# phone.net
KiCad netlist of a schematic drawn in Altium Designer
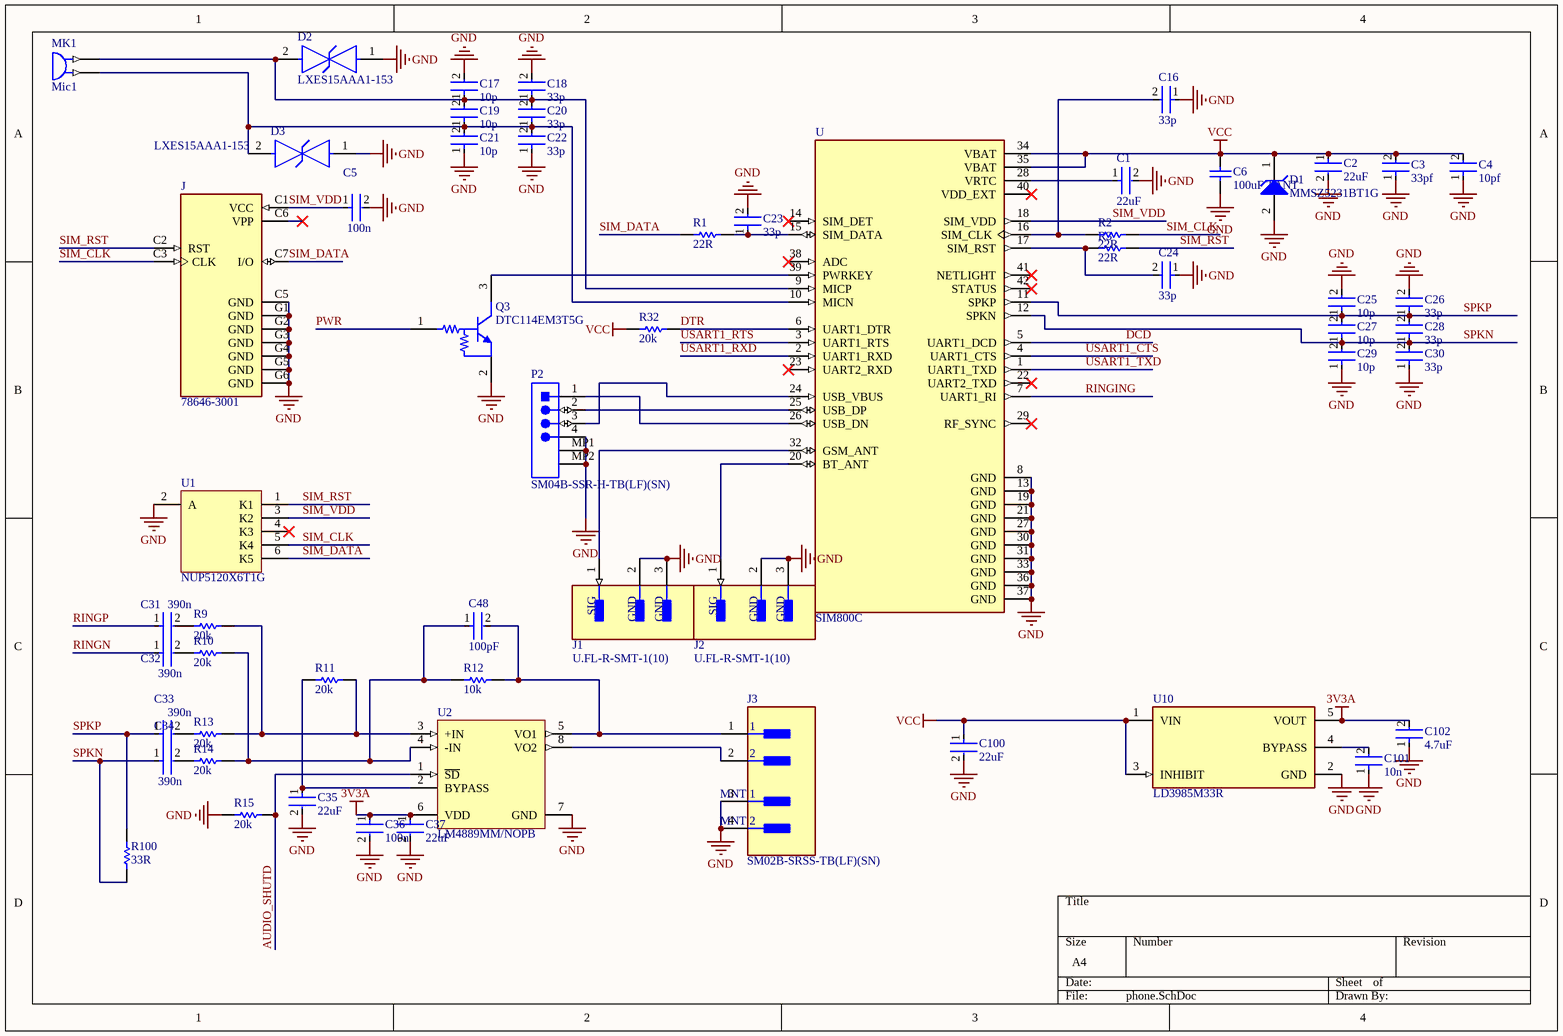
[diagram p0: phone.SchDoc]

(export (version "E")
  (design (tool "Eeschema 10.0.6"))
  (components
    (comp (ref "C1")
      (value "22uF")
      (footprint "FP-GRM21B-0_15-MFG")
      (description "Chip Multilayer Ceramic Capacitors for General Purpose, 0805, 22uF, X5R, 15%, 20%, 6.3V")
      (fields (field (name "VOLTAGE") "6.3V") (field (name "TOLERANCE") "20%"))
      (libsource (lib "Altium Content Vault") (part "b4654b650e69147ec39a6b967a45e02"))
    )
    (comp (ref "C2")
      (value "22uF")
      (footprint "FP-GRM21B-0_15-MFG")
      (description "Chip Multilayer Ceramic Capacitors for General Purpose, 0805, 22uF, X5R, 15%, 20%, 6.3V")
      (fields (field (name "VOLTAGE") "6.3V") (field (name "TOLERANCE") "20%"))
      (libsource (lib "Altium Content Vault") (part "b4654b650e69147ec39a6b967a45e02"))
    )
    (comp (ref "C3")
      (value "33pf")
      (footprint "FP-GRM155-0_05-IPC_A")
      (description "Chip Multilayer Ceramic Capacitors for General Purpose, 0402, 470pF, C0G, 30ppm/°C, 5%, 50V")
      (fields (field (name "VOLTAGE") "50V") (field (name "TOLERANCE") "5%"))
      (libsource (lib "Altium Content Vault") (part "02cd4be3c70576c341d710602a673aa"))
    )
    (comp (ref "C4")
      (value "10pf")
      (footprint "FP-GRM155-0_05-IPC_A")
      (description "Chip Multilayer Ceramic Capacitors for General Purpose, 0402, 470pF, C0G, 30ppm/°C, 5%, 50V")
      (fields (field (name "VOLTAGE") "50V") (field (name "TOLERANCE") "5%"))
      (libsource (lib "Altium Content Vault") (part "02cd4be3c70576c341d710602a673aa"))
    )
    (comp (ref "C5")
      (value "100n")
      (footprint "FP-GRM155-0_05-IPC_A")
      (description "Chip Multilayer Ceramic Capacitors for General Purpose, 0402, 470pF, C0G, 30ppm/°C, 5%, 50V")
      (fields (field (name "VOLTAGE") "50V") (field (name "TOLERANCE") "5%"))
      (libsource (lib "Altium Content Vault") (part "02cd4be3c70576c341d710602a673aa"))
    )
    (comp (ref "C6")
      (value "100uF TANT")
      (footprint "CAPMP3525X20N")
      (description "Capacitor")
      (libsource (lib "Simulation Generic Components") (part "Capacitor"))
    )
    (comp (ref "C16")
      (value "33p")
      (footprint "FP-GRM155-0_05-IPC_A")
      (description "Chip Multilayer Ceramic Capacitors for General Purpose, 0402, 470pF, C0G, 30ppm/°C, 5%, 50V")
      (fields (field (name "VOLTAGE") "50V") (field (name "TOLERANCE") "5%"))
      (libsource (lib "Altium Content Vault") (part "02cd4be3c70576c341d710602a673aa"))
    )
    (comp (ref "C17")
      (value "10p")
      (footprint "FP-GRM155-0_05-IPC_A")
      (description "Chip Multilayer Ceramic Capacitors for General Purpose, 0402, 470pF, C0G, 30ppm/°C, 5%, 50V")
      (fields (field (name "VOLTAGE") "50V") (field (name "TOLERANCE") "5%"))
      (libsource (lib "Altium Content Vault") (part "02cd4be3c70576c341d710602a673aa"))
    )
    (comp (ref "C18")
      (value "33p")
      (footprint "FP-GRM155-0_05-IPC_A")
      (description "Chip Multilayer Ceramic Capacitors for General Purpose, 0402, 470pF, C0G, 30ppm/°C, 5%, 50V")
      (fields (field (name "VOLTAGE") "50V") (field (name "TOLERANCE") "5%"))
      (libsource (lib "Altium Content Vault") (part "02cd4be3c70576c341d710602a673aa"))
    )
    (comp (ref "C19")
      (value "10p")
      (footprint "FP-GRM155-0_05-IPC_A")
      (description "Chip Multilayer Ceramic Capacitors for General Purpose, 0402, 470pF, C0G, 30ppm/°C, 5%, 50V")
      (fields (field (name "VOLTAGE") "50V") (field (name "TOLERANCE") "5%"))
      (libsource (lib "Altium Content Vault") (part "02cd4be3c70576c341d710602a673aa"))
    )
    (comp (ref "C20")
      (value "33p")
      (footprint "FP-GRM155-0_05-IPC_A")
      (description "Chip Multilayer Ceramic Capacitors for General Purpose, 0402, 470pF, C0G, 30ppm/°C, 5%, 50V")
      (fields (field (name "VOLTAGE") "50V") (field (name "TOLERANCE") "5%"))
      (libsource (lib "Altium Content Vault") (part "02cd4be3c70576c341d710602a673aa"))
    )
    (comp (ref "C21")
      (value "10p")
      (footprint "FP-GRM155-0_05-IPC_A")
      (description "Chip Multilayer Ceramic Capacitors for General Purpose, 0402, 470pF, C0G, 30ppm/°C, 5%, 50V")
      (fields (field (name "VOLTAGE") "50V") (field (name "TOLERANCE") "5%"))
      (libsource (lib "Altium Content Vault") (part "02cd4be3c70576c341d710602a673aa"))
    )
    (comp (ref "C22")
      (value "33p")
      (footprint "FP-GRM155-0_05-IPC_A")
      (description "Chip Multilayer Ceramic Capacitors for General Purpose, 0402, 470pF, C0G, 30ppm/°C, 5%, 50V")
      (fields (field (name "VOLTAGE") "50V") (field (name "TOLERANCE") "5%"))
      (libsource (lib "Altium Content Vault") (part "02cd4be3c70576c341d710602a673aa"))
    )
    (comp (ref "C23")
      (value "33p")
      (footprint "FP-GRM155-0_05-IPC_A")
      (description "Chip Multilayer Ceramic Capacitors for General Purpose, 0402, 470pF, C0G, 30ppm/°C, 5%, 50V")
      (fields (field (name "VOLTAGE") "50V") (field (name "TOLERANCE") "5%"))
      (libsource (lib "Altium Content Vault") (part "02cd4be3c70576c341d710602a673aa"))
    )
    (comp (ref "C24")
      (value "33p")
      (footprint "FP-GRM155-0_05-IPC_A")
      (description "Chip Multilayer Ceramic Capacitors for General Purpose, 0402, 470pF, C0G, 30ppm/°C, 5%, 50V")
      (fields (field (name "VOLTAGE") "50V") (field (name "TOLERANCE") "5%"))
      (libsource (lib "Altium Content Vault") (part "02cd4be3c70576c341d710602a673aa"))
    )
    (comp (ref "C25")
      (value "10p")
      (footprint "FP-GRM155-0_05-IPC_A")
      (description "Chip Multilayer Ceramic Capacitors for General Purpose, 0402, 470pF, C0G, 30ppm/°C, 5%, 50V")
      (fields (field (name "VOLTAGE") "50V") (field (name "TOLERANCE") "5%"))
      (libsource (lib "Altium Content Vault") (part "02cd4be3c70576c341d710602a673aa"))
    )
    (comp (ref "C26")
      (value "33p")
      (footprint "FP-GRM155-0_05-IPC_A")
      (description "Chip Multilayer Ceramic Capacitors for General Purpose, 0402, 470pF, C0G, 30ppm/°C, 5%, 50V")
      (fields (field (name "VOLTAGE") "50V") (field (name "TOLERANCE") "5%"))
      (libsource (lib "Altium Content Vault") (part "02cd4be3c70576c341d710602a673aa"))
    )
    (comp (ref "C27")
      (value "10p")
      (footprint "FP-GRM155-0_05-IPC_A")
      (description "Chip Multilayer Ceramic Capacitors for General Purpose, 0402, 470pF, C0G, 30ppm/°C, 5%, 50V")
      (fields (field (name "VOLTAGE") "50V") (field (name "TOLERANCE") "5%"))
      (libsource (lib "Altium Content Vault") (part "02cd4be3c70576c341d710602a673aa"))
    )
    (comp (ref "C28")
      (value "33p")
      (footprint "FP-GRM155-0_05-IPC_A")
      (description "Chip Multilayer Ceramic Capacitors for General Purpose, 0402, 470pF, C0G, 30ppm/°C, 5%, 50V")
      (fields (field (name "VOLTAGE") "50V") (field (name "TOLERANCE") "5%"))
      (libsource (lib "Altium Content Vault") (part "02cd4be3c70576c341d710602a673aa"))
    )
    (comp (ref "C29")
      (value "10p")
      (footprint "FP-GRM155-0_05-IPC_A")
      (description "Chip Multilayer Ceramic Capacitors for General Purpose, 0402, 470pF, C0G, 30ppm/°C, 5%, 50V")
      (fields (field (name "VOLTAGE") "50V") (field (name "TOLERANCE") "5%"))
      (libsource (lib "Altium Content Vault") (part "02cd4be3c70576c341d710602a673aa"))
    )
    (comp (ref "C30")
      (value "33p")
      (footprint "FP-GRM155-0_05-IPC_A")
      (description "Chip Multilayer Ceramic Capacitors for General Purpose, 0402, 470pF, C0G, 30ppm/°C, 5%, 50V")
      (fields (field (name "VOLTAGE") "50V") (field (name "TOLERANCE") "5%"))
      (libsource (lib "Altium Content Vault") (part "02cd4be3c70576c341d710602a673aa"))
    )
    (comp (ref "C31")
      (value "390n")
      (footprint "FP-GRM155-0_05-IPC_A")
      (description "Chip Multilayer Ceramic Capacitors for General Purpose, 0402, 470pF, C0G, 30ppm/°C, 5%, 50V")
      (fields (field (name "VOLTAGE") "50V") (field (name "TOLERANCE") "5%"))
      (libsource (lib "Altium Content Vault") (part "02cd4be3c70576c341d710602a673aa"))
    )
    (comp (ref "C32")
      (value "390n")
      (footprint "FP-GRM155-0_05-IPC_A")
      (description "Chip Multilayer Ceramic Capacitors for General Purpose, 0402, 470pF, C0G, 30ppm/°C, 5%, 50V")
      (fields (field (name "VOLTAGE") "50V") (field (name "TOLERANCE") "5%"))
      (libsource (lib "Altium Content Vault") (part "02cd4be3c70576c341d710602a673aa"))
    )
    (comp (ref "C33")
      (value "390n")
      (footprint "FP-GRM155-0_05-IPC_A")
      (description "Chip Multilayer Ceramic Capacitors for General Purpose, 0402, 470pF, C0G, 30ppm/°C, 5%, 50V")
      (fields (field (name "VOLTAGE") "50V") (field (name "TOLERANCE") "5%"))
      (libsource (lib "Altium Content Vault") (part "02cd4be3c70576c341d710602a673aa"))
    )
    (comp (ref "C34")
      (value "390n")
      (footprint "FP-GRM155-0_05-IPC_A")
      (description "Chip Multilayer Ceramic Capacitors for General Purpose, 0402, 470pF, C0G, 30ppm/°C, 5%, 50V")
      (fields (field (name "VOLTAGE") "50V") (field (name "TOLERANCE") "5%"))
      (libsource (lib "Altium Content Vault") (part "02cd4be3c70576c341d710602a673aa"))
    )
    (comp (ref "C35")
      (value "22uF")
      (footprint "FP-GRM21B-0_15-MFG")
      (description "Chip Multilayer Ceramic Capacitors for General Purpose, 0805, 22uF, X5R, 15%, 20%, 6.3V")
      (fields (field (name "VOLTAGE") "6.3V") (field (name "TOLERANCE") "20%"))
      (libsource (lib "Altium Content Vault") (part "b4654b650e69147ec39a6b967a45e02"))
    )
    (comp (ref "C36")
      (value "100n")
      (footprint "FP-GRM155-0_05-IPC_A")
      (description "Chip Multilayer Ceramic Capacitors for General Purpose, 0402, 470pF, C0G, 30ppm/°C, 5%, 50V")
      (fields (field (name "VOLTAGE") "50V") (field (name "TOLERANCE") "5%"))
      (libsource (lib "Altium Content Vault") (part "02cd4be3c70576c341d710602a673aa"))
    )
    (comp (ref "C37")
      (value "22uF")
      (footprint "FP-GRM21B-0_15-MFG")
      (description "Chip Multilayer Ceramic Capacitors for General Purpose, 0805, 22uF, X5R, 15%, 20%, 6.3V")
      (fields (field (name "VOLTAGE") "6.3V") (field (name "TOLERANCE") "20%"))
      (libsource (lib "Altium Content Vault") (part "b4654b650e69147ec39a6b967a45e02"))
    )
    (comp (ref "C48")
      (value "100pF")
      (footprint "FP-GRM155-0_05-IPC_A")
      (description "Chip Multilayer Ceramic Capacitors for General Purpose, 0402, 470pF, C0G, 30ppm/°C, 5%, 50V")
      (fields (field (name "VOLTAGE") "50V") (field (name "TOLERANCE") "5%"))
      (libsource (lib "Altium Content Vault") (part "02cd4be3c70576c341d710602a673aa"))
    )
    (comp (ref "C100")
      (value "22uF")
      (footprint "FP-GRM21B-0_15-MFG")
      (description "Chip Multilayer Ceramic Capacitors for General Purpose, 0805, 22uF, X5R, 15%, 20%, 6.3V")
      (fields (field (name "VOLTAGE") "6.3V") (field (name "TOLERANCE") "20%"))
      (libsource (lib "Altium Content Vault") (part "b4654b650e69147ec39a6b967a45e02"))
    )
    (comp (ref "C101")
      (value "10n")
      (footprint "FP-GRM155-0_05-IPC_A")
      (description "Chip Multilayer Ceramic Capacitors for General Purpose, 0402, 470pF, C0G, 30ppm/°C, 5%, 50V")
      (fields (field (name "VOLTAGE") "50V") (field (name "TOLERANCE") "5%"))
      (libsource (lib "Altium Content Vault") (part "02cd4be3c70576c341d710602a673aa"))
    )
    (comp (ref "C102")
      (value "4.7uF")
      (footprint "FP-GRM188-0_1-e0_2_0_55-IPC_A")
      (description "Chip Multilayer Ceramic Capacitors for General Purpose, 0603, 10uF, X5R, 15%, 20%, 6.3V")
      (fields (field (name "VOLTAGE") "6.3V") (field (name "TOLERANCE") "20%"))
      (libsource (lib "Altium Content Vault") (part "02cd4be3c70576c341d710602a673aa"))
    )
    (comp (ref "D1")
      (value "MMSZ5231BT1G")
      (footprint "ONSC-SOD-123-2-425-04_V")
      (description "Zener Voltage Regulator, 500 mW, 2-Pin SOD-123, Pb-Free, Tape and Reel")
      (fields (field (name "MANUFACTURER") "On Semiconductor"))
      (libsource (lib "Altium Content Vault") (part "ONSC-K1A2-2"))
    )
    (comp (ref "D2")
      (value "LXES15AAA1-153")
      (footprint "FP-LXES15-MFG")
      (description "TVS DIODE 4V 1005")
      (libsource (lib "Altium Content Vault") (part "876f4347bf90aa6f500f43e3cd03972"))
    )
    (comp (ref "D3")
      (value "LXES15AAA1-153")
      (footprint "FP-LXES15-MFG")
      (description "TVS DIODE 4V 1005")
      (libsource (lib "Altium Content Vault") (part "876f4347bf90aa6f500f43e3cd03972"))
    )
    (comp (ref "J")
      (value "78646-3001")
      (footprint "MOLEX_78646-3001")
      (description "6 Position Card Connector Micro SIM Surface Mount, Right Angle Gold")
      (fields (field (name "MF") "Molex"))
      (libsource (lib "SnapEDAsch") (part "78646-3001"))
    )
    (comp (ref "J1")
      (value "U.FL-R-SMT-1(10)")
      (footprint "FP-U_FL-R-SMT-1_10-MFG")
      (description "CONN U.FL RCPT STR 50 OHM SMD")
      (libsource (lib "Altium Content Vault") (part "7158abf7d987fa84906f6fb0d115710"))
    )
    (comp (ref "J2")
      (value "U.FL-R-SMT-1(10)")
      (footprint "FP-U_FL-R-SMT-1_10-MFG")
      (description "CONN U.FL RCPT STR 50 OHM SMD")
      (libsource (lib "Altium Content Vault") (part "7158abf7d987fa84906f6fb0d115710"))
    )
    (comp (ref "J3")
      (value "SM02B-SRSS-TB(LF)(SN)")
      (footprint "FP-SM02B-SRSS-TB_LF_SN-0")
      (description "CONN HEADER SMD R/A 2POS 1MM")
      (libsource (lib "Altium Content Vault") (part "e34efe21362d63d7198b5d2c73e37bd"))
    )
    (comp (ref "MK1")
      (value "Mic1")
      (footprint "4015")
      (description "Microphone")
      (fields (field (name "PUBLISHER") "Altium Limited"))
      (libsource (lib "Miscellaneous Devices") (part "Mic1"))
    )
    (comp (ref "P2")
      (value "SM04B-SSR-H-TB(LF)(SN)")
      (footprint "JST-SM04B-SSR-H-TB_V")
      (description "SSR Connector, Pitch 1 mm, 1 x 4 Position, Height 2 mm, -20 to 85 degC, RoHS, Tape and Reel")
      (fields (field (name "MANUFACTURER") "JST"))
      (libsource (lib "Altium Content Vault") (part "CN-1P-2M-R4_A"))
    )
    (comp (ref "Q3")
      (value "DTC114EM3T5G")
      (footprint "ONSC-SOT-723-3-631AA-01_V")
      (fields (field (name "MANUFACTURER") "On Semiconductor"))
      (libsource (lib "Altium Content Vault") (part "ONSC-BRT-NPN-B1E2C3-3"))
    )
    (comp (ref "R1")
      (value "22R")
      (footprint "RESC1005X40X25NL05T10")
      (fields (field (name "MANUFACTURER") "Yageo / Phycomp") (field (name "PART NUMBER") "RC0402JR-070RL"))
      (libsource (lib "Altium Content Vault") (part "RES"))
    )
    (comp (ref "R2")
      (value "22R")
      (footprint "RESC1005X40X25NL05T10")
      (fields (field (name "MANUFACTURER") "Yageo / Phycomp") (field (name "PART NUMBER") "RC0402JR-070RL"))
      (libsource (lib "Altium Content Vault") (part "RES"))
    )
    (comp (ref "R3")
      (value "22R")
      (footprint "RESC1005X40X25NL05T10")
      (fields (field (name "MANUFACTURER") "Yageo / Phycomp") (field (name "PART NUMBER") "RC0402JR-070RL"))
      (libsource (lib "Altium Content Vault") (part "RES"))
    )
    (comp (ref "R9")
      (value "20k")
      (footprint "RESC1005X40X25NL05T10")
      (fields (field (name "MANUFACTURER") "Yageo / Phycomp") (field (name "PART NUMBER") "RC0402JR-070RL"))
      (libsource (lib "Altium Content Vault") (part "RES"))
    )
    (comp (ref "R10")
      (value "20k")
      (footprint "RESC1005X40X25NL05T10")
      (fields (field (name "MANUFACTURER") "Yageo / Phycomp") (field (name "PART NUMBER") "RC0402JR-070RL"))
      (libsource (lib "Altium Content Vault") (part "RES"))
    )
    (comp (ref "R11")
      (value "20k")
      (footprint "RESC1005X40X25NL05T10")
      (fields (field (name "MANUFACTURER") "Yageo / Phycomp") (field (name "PART NUMBER") "RC0402JR-070RL"))
      (libsource (lib "Altium Content Vault") (part "RES"))
    )
    (comp (ref "R12")
      (value "10k")
      (footprint "RESC1005X40X25NL05T10")
      (fields (field (name "MANUFACTURER") "Yageo / Phycomp") (field (name "PART NUMBER") "RC0402JR-070RL"))
      (libsource (lib "Altium Content Vault") (part "RES"))
    )
    (comp (ref "R13")
      (value "20k")
      (footprint "RESC1005X40X25NL05T10")
      (fields (field (name "MANUFACTURER") "Yageo / Phycomp") (field (name "PART NUMBER") "RC0402JR-070RL"))
      (libsource (lib "Altium Content Vault") (part "RES"))
    )
    (comp (ref "R14")
      (value "20k")
      (footprint "RESC1005X40X25NL05T10")
      (fields (field (name "MANUFACTURER") "Yageo / Phycomp") (field (name "PART NUMBER") "RC0402JR-070RL"))
      (libsource (lib "Altium Content Vault") (part "RES"))
    )
    (comp (ref "R15")
      (value "20k")
      (footprint "RESC1005X40X25NL05T10")
      (fields (field (name "MANUFACTURER") "Yageo / Phycomp") (field (name "PART NUMBER") "RC0402JR-070RL"))
      (libsource (lib "Altium Content Vault") (part "RES"))
    )
    (comp (ref "R32")
      (value "20k")
      (footprint "RESC1005X40X25NL05T10")
      (fields (field (name "MANUFACTURER") "Yageo / Phycomp") (field (name "PART NUMBER") "RC0402JR-070RL"))
      (libsource (lib "Altium Content Vault") (part "RES"))
    )
    (comp (ref "R100")
      (value "33R")
      (footprint "RESC1005X40X25NL05T10")
      (fields (field (name "MANUFACTURER") "Yageo / Phycomp") (field (name "PART NUMBER") "RC0402JR-070RL"))
      (libsource (lib "Altium Content Vault") (part "RES"))
    )
    (comp (ref "U")
      (value "SIM800C")
      (footprint "LCC110P1570X1760X250-42N-NEW")
      (description "Module: GSM/Bluetooth; GPRS; 2G; 1800MHz, 900MHz; 85.6kbps; SMD")
      (fields (field (name "MF") "Simcom"))
      (libsource (lib "SIM800C") (part "SIM800C"))
    )
    (comp (ref "U1")
      (value "NUP5120X6T1G")
      (footprint "ONSC-SOT-563-6-463A-01_V")
      (description "5-Line Transient Voltage Suppressor Array, 6-Pin SOT-563, Pb-Free, Tape and Reel")
      (fields (field (name "MANUFACTURER") "On Semiconductor"))
      (libsource (lib "Altium Content Vault") (part "ONSC-K1A2K3K4K5K6-6"))
    )
    (comp (ref "U2")
      (value "LM4889MM/NOPB")
      (footprint "DGK0008A_L")
      (description "1W Audio Power Amplifier, 8-pin Mini SOIC, Pb-Free")
      (fields (field (name "MANUFACTURER") "Texas Instruments"))
      (libsource (lib "Altium Content Vault") (part "AMP-APA-LM4876-8"))
    )
    (comp (ref "U10")
      (value "LD3985M33R")
      (footprint "FP-SOT23-5L-7049676-MFG")
      (description "IC REG LINEAR 3.3V 150MA SOT23-5")
      (libsource (lib "Altium Content Vault") (part "aba04f4e281572ab958dbcc456c8333"))
    )
  )
  (nets
    (net (code "1") (name "/AUDIO_SHUTD") (class "Default")
      (node (ref "R15") (pin "2") (pinfunction "2_2") (pintype "passive"))
      (node (ref "U2") (pin "1") (pinfunction "~{SD}_1") (pintype "input"))
    )
    (net (code "2") (name "/DCD") (class "Default")
      (node (ref "U") (pin "5") (pinfunction "UART1_DCD_5") (pintype "output"))
    )
    (net (code "3") (name "/DTR") (class "Default")
      (node (ref "R32") (pin "2") (pinfunction "2_2") (pintype "passive"))
      (node (ref "U") (pin "6") (pinfunction "UART1_DTR_6") (pintype "input"))
    )
    (net (code "4") (name "/PWR") (class "Default")
      (node (ref "Q3") (pin "1") (pinfunction "B_1") (pintype "passive"))
    )
    (net (code "5") (name "/RINGING") (class "Default")
      (node (ref "U") (pin "7") (pinfunction "UART1_RI_7") (pintype "output"))
    )
    (net (code "6") (name "/RINGN") (class "Default")
      (node (ref "C32") (pin "1") (pinfunction "1_1") (pintype "passive"))
    )
    (net (code "7") (name "/RINGP") (class "Default")
      (node (ref "C31") (pin "1") (pinfunction "1_1") (pintype "passive"))
    )
    (net (code "8") (name "/SIM_CLK") (class "Default")
      (node (ref "J") (pin "C3") (pinfunction "CLK_C3") (pintype "input"))
      (node (ref "R2") (pin "2") (pinfunction "2_2") (pintype "passive"))
      (node (ref "U1") (pin "5") (pinfunction "K4_5") (pintype "passive"))
    )
    (net (code "9") (name "/SIM_DATA") (class "Default")
      (node (ref "J") (pin "C7") (pinfunction "I/O_C7") (pintype "bidirectional"))
      (node (ref "R1") (pin "1") (pinfunction "1_1") (pintype "passive"))
      (node (ref "U1") (pin "6") (pinfunction "K5_6") (pintype "passive"))
    )
    (net (code "10") (name "/SIM_RST") (class "Default")
      (node (ref "J") (pin "C2") (pinfunction "RST_C2") (pintype "input"))
      (node (ref "R3") (pin "2") (pinfunction "2_2") (pintype "passive"))
      (node (ref "U1") (pin "1") (pinfunction "K1_1") (pintype "passive"))
    )
    (net (code "11") (name "/SIM_VDD") (class "Default")
      (node (ref "C5") (pin "1") (pinfunction "1_1") (pintype "passive"))
      (node (ref "J") (pin "C1") (pinfunction "VCC_C1") (pintype "input"))
      (node (ref "U") (pin "18") (pinfunction "SIM_VDD_18") (pintype "output"))
      (node (ref "U1") (pin "3") (pinfunction "K2_3") (pintype "passive"))
    )
    (net (code "12") (name "/SPKN") (class "Default")
      (node (ref "C27") (pin "1") (pinfunction "1_1") (pintype "passive"))
      (node (ref "C28") (pin "1") (pinfunction "1_1") (pintype "passive"))
      (node (ref "C29") (pin "2") (pinfunction "2_2") (pintype "passive"))
      (node (ref "C30") (pin "2") (pinfunction "2_2") (pintype "passive"))
      (node (ref "C34") (pin "1") (pinfunction "1_1") (pintype "passive"))
      (node (ref "R100") (pin "1") (pinfunction "1_1") (pintype "passive"))
      (node (ref "U") (pin "12") (pinfunction "SPKN_12") (pintype "output"))
    )
    (net (code "13") (name "/SPKP") (class "Default")
      (node (ref "C25") (pin "1") (pinfunction "1_1") (pintype "passive"))
      (node (ref "C26") (pin "1") (pinfunction "1_1") (pintype "passive"))
      (node (ref "C27") (pin "2") (pinfunction "2_2") (pintype "passive"))
      (node (ref "C28") (pin "2") (pinfunction "2_2") (pintype "passive"))
      (node (ref "C33") (pin "1") (pinfunction "1_1") (pintype "passive"))
      (node (ref "R100") (pin "2") (pinfunction "2_2") (pintype "passive"))
      (node (ref "U") (pin "11") (pinfunction "SPKP_11") (pintype "output"))
    )
    (net (code "14") (name "/USART1_CTS") (class "Default")
      (node (ref "U") (pin "4") (pinfunction "UART1_CTS_4") (pintype "output"))
    )
    (net (code "15") (name "/USART1_RTS") (class "Default")
      (node (ref "U") (pin "3") (pinfunction "UART1_RTS_3") (pintype "input"))
    )
    (net (code "16") (name "/USART1_RXD") (class "Default")
      (node (ref "U") (pin "2") (pinfunction "UART1_RXD_2") (pintype "input"))
    )
    (net (code "17") (name "/USART1_TXD") (class "Default")
      (node (ref "U") (pin "1") (pinfunction "UART1_TXD_1") (pintype "output"))
    )
    (net (code "18") (name "3V3A") (class "Default")
      (node (ref "C102") (pin "2") (pinfunction "2_2") (pintype "passive"))
      (node (ref "C36") (pin "1") (pinfunction "1_1") (pintype "passive"))
      (node (ref "C37") (pin "1") (pinfunction "1_1") (pintype "passive"))
      (node (ref "U10") (pin "5") (pinfunction "VOUT_5") (pintype "passive"))
      (node (ref "U2") (pin "6") (pinfunction "VDD_6") (pintype "power_in"))
    )
    (net (code "19") (name "GND") (class "Default")
      (node (ref "C1") (pin "2") (pinfunction "2_2") (pintype "passive"))
      (node (ref "C100") (pin "2") (pinfunction "2_2") (pintype "passive"))
      (node (ref "C101") (pin "1") (pinfunction "1_1") (pintype "passive"))
      (node (ref "C102") (pin "1") (pinfunction "1_1") (pintype "passive"))
      (node (ref "C16") (pin "1") (pinfunction "1_1") (pintype "passive"))
      (node (ref "C17") (pin "2") (pinfunction "2_2") (pintype "passive"))
      (node (ref "C18") (pin "2") (pinfunction "2_2") (pintype "passive"))
      (node (ref "C2") (pin "2") (pinfunction "2_2") (pintype "passive"))
      (node (ref "C21") (pin "1") (pinfunction "1_1") (pintype "passive"))
      (node (ref "C22") (pin "1") (pinfunction "1_1") (pintype "passive"))
      (node (ref "C23") (pin "2") (pinfunction "2_2") (pintype "passive"))
      (node (ref "C24") (pin "1") (pinfunction "1_1") (pintype "passive"))
      (node (ref "C25") (pin "2") (pinfunction "2_2") (pintype "passive"))
      (node (ref "C26") (pin "2") (pinfunction "2_2") (pintype "passive"))
      (node (ref "C29") (pin "1") (pinfunction "1_1") (pintype "passive"))
      (node (ref "C3") (pin "1") (pinfunction "1_1") (pintype "passive"))
      (node (ref "C30") (pin "1") (pinfunction "1_1") (pintype "passive"))
      (node (ref "C35") (pin "2") (pinfunction "2_2") (pintype "passive"))
      (node (ref "C36") (pin "2") (pinfunction "2_2") (pintype "passive"))
      (node (ref "C37") (pin "2") (pinfunction "2_2") (pintype "passive"))
      (node (ref "C4") (pin "1") (pinfunction "1_1") (pintype "passive"))
      (node (ref "C5") (pin "2") (pinfunction "2_2") (pintype "passive"))
      (node (ref "C6") (pin "2") (pinfunction "2_2") (pintype "passive"))
      (node (ref "D1") (pin "2") (pinfunction "A_2") (pintype "passive"))
      (node (ref "D2") (pin "1") (pinfunction "1_1") (pintype "passive"))
      (node (ref "D3") (pin "1") (pinfunction "1_1") (pintype "passive"))
      (node (ref "J") (pin "C5") (pinfunction "GND_C5") (pintype "power_in"))
      (node (ref "J") (pin "G1") (pinfunction "GND_G1") (pintype "power_in"))
      (node (ref "J") (pin "G2") (pinfunction "GND_G2") (pintype "power_in"))
      (node (ref "J") (pin "G3") (pinfunction "GND_G3") (pintype "power_in"))
      (node (ref "J") (pin "G4") (pinfunction "GND_G4") (pintype "power_in"))
      (node (ref "J") (pin "G5") (pinfunction "GND_G5") (pintype "power_in"))
      (node (ref "J") (pin "G6") (pinfunction "GND_G6") (pintype "power_in"))
      (node (ref "J1") (pin "2") (pinfunction "GND_2") (pintype "power_in"))
      (node (ref "J1") (pin "3") (pinfunction "GND_3") (pintype "power_in"))
      (node (ref "J2") (pin "2") (pinfunction "GND_2") (pintype "power_in"))
      (node (ref "J2") (pin "3") (pinfunction "GND_3") (pintype "power_in"))
      (node (ref "J3") (pin "3") (pinfunction "MNT_1_3") (pintype "passive"))
      (node (ref "J3") (pin "4") (pinfunction "MNT_2_4") (pintype "passive"))
      (node (ref "P2") (pin "4") (pinfunction "4_4") (pintype "passive"))
      (node (ref "P2") (pin "MP1") (pinfunction "MP1_MP1") (pintype "passive"))
      (node (ref "P2") (pin "MP2") (pinfunction "MP2_MP2") (pintype "passive"))
      (node (ref "Q3") (pin "2") (pinfunction "E_2") (pintype "passive"))
      (node (ref "R15") (pin "1") (pinfunction "1_1") (pintype "passive"))
      (node (ref "U") (pin "13") (pinfunction "GND_13") (pintype "power_in"))
      (node (ref "U") (pin "19") (pinfunction "GND_19") (pintype "power_in"))
      (node (ref "U") (pin "21") (pinfunction "GND_21") (pintype "power_in"))
      (node (ref "U") (pin "27") (pinfunction "GND_27") (pintype "power_in"))
      (node (ref "U") (pin "30") (pinfunction "GND_30") (pintype "power_in"))
      (node (ref "U") (pin "31") (pinfunction "GND_31") (pintype "power_in"))
      (node (ref "U") (pin "33") (pinfunction "GND_33") (pintype "power_in"))
      (node (ref "U") (pin "36") (pinfunction "GND_36") (pintype "power_in"))
      (node (ref "U") (pin "37") (pinfunction "GND_37") (pintype "power_in"))
      (node (ref "U") (pin "8") (pinfunction "GND_8") (pintype "power_in"))
      (node (ref "U1") (pin "2") (pinfunction "A_2") (pintype "passive"))
      (node (ref "U10") (pin "2") (pinfunction "GND_2") (pintype "power_in"))
      (node (ref "U2") (pin "7") (pinfunction "GND_7") (pintype "power_in"))
    )
    (net (code "20") (name "Net-(C31-Pad2)") (class "Default")
      (node (ref "C31") (pin "2") (pinfunction "2_2") (pintype "passive"))
      (node (ref "R9") (pin "1") (pinfunction "1_1") (pintype "passive"))
    )
    (net (code "21") (name "Net-(C32-Pad2)") (class "Default")
      (node (ref "C32") (pin "2") (pinfunction "2_2") (pintype "passive"))
      (node (ref "R10") (pin "1") (pinfunction "1_1") (pintype "passive"))
    )
    (net (code "22") (name "Net-(C33-Pad2)") (class "Default")
      (node (ref "C33") (pin "2") (pinfunction "2_2") (pintype "passive"))
      (node (ref "R13") (pin "1") (pinfunction "1_1") (pintype "passive"))
    )
    (net (code "23") (name "Net-(C34-Pad2)") (class "Default")
      (node (ref "C34") (pin "2") (pinfunction "2_2") (pintype "passive"))
      (node (ref "R14") (pin "1") (pinfunction "1_1") (pintype "passive"))
    )
    (net (code "24") (name "Net-(J1-SIG)") (class "Default")
      (node (ref "J1") (pin "1") (pinfunction "SIG_1") (pintype "input"))
      (node (ref "U") (pin "32") (pinfunction "GSM_ANT_32") (pintype "bidirectional"))
    )
    (net (code "25") (name "Net-(J2-SIG)") (class "Default")
      (node (ref "J2") (pin "1") (pinfunction "SIG_1") (pintype "input"))
      (node (ref "U") (pin "20") (pinfunction "BT_ANT_20") (pintype "bidirectional"))
    )
    (net (code "26") (name "Net-(Q3-C)") (class "Default")
      (node (ref "Q3") (pin "3") (pinfunction "C_3") (pintype "passive"))
      (node (ref "U") (pin "39") (pinfunction "PWRKEY_39") (pintype "input"))
    )
    (net (code "27") (name "Net-(U-MICN)") (class "Default")
      (node (ref "C19") (pin "1") (pinfunction "1_1") (pintype "passive"))
      (node (ref "C20") (pin "1") (pinfunction "1_1") (pintype "passive"))
      (node (ref "C21") (pin "2") (pinfunction "2_2") (pintype "passive"))
      (node (ref "C22") (pin "2") (pinfunction "2_2") (pintype "passive"))
      (node (ref "D3") (pin "2") (pinfunction "2_2") (pintype "passive"))
      (node (ref "MK1") (pin "2") (pinfunction "2_2") (pintype "output"))
      (node (ref "U") (pin "10") (pinfunction "MICN_10") (pintype "input"))
    )
    (net (code "28") (name "Net-(U-MICP)") (class "Default")
      (node (ref "C17") (pin "1") (pinfunction "1_1") (pintype "passive"))
      (node (ref "C18") (pin "1") (pinfunction "1_1") (pintype "passive"))
      (node (ref "C19") (pin "2") (pinfunction "2_2") (pintype "passive"))
      (node (ref "C20") (pin "2") (pinfunction "2_2") (pintype "passive"))
      (node (ref "D2") (pin "2") (pinfunction "2_2") (pintype "passive"))
      (node (ref "MK1") (pin "1") (pinfunction "1_1") (pintype "output"))
      (node (ref "U") (pin "9") (pinfunction "MICP_9") (pintype "input"))
    )
    (net (code "29") (name "Net-(U-SIM_CLK)") (class "Default")
      (node (ref "C16") (pin "2") (pinfunction "2_2") (pintype "passive"))
      (node (ref "R2") (pin "1") (pinfunction "1_1") (pintype "passive"))
      (node (ref "U") (pin "16") (pinfunction "SIM_CLK_16") (pintype "output"))
    )
    (net (code "30") (name "Net-(U-SIM_DATA)") (class "Default")
      (node (ref "C23") (pin "1") (pinfunction "1_1") (pintype "passive"))
      (node (ref "R1") (pin "2") (pinfunction "2_2") (pintype "passive"))
      (node (ref "U") (pin "15") (pinfunction "SIM_DATA_15") (pintype "bidirectional"))
    )
    (net (code "31") (name "Net-(U-SIM_RST)") (class "Default")
      (node (ref "C24") (pin "2") (pinfunction "2_2") (pintype "passive"))
      (node (ref "R3") (pin "1") (pinfunction "1_1") (pintype "passive"))
      (node (ref "U") (pin "17") (pinfunction "SIM_RST_17") (pintype "output"))
    )
    (net (code "32") (name "Net-(U-USB_DN)") (class "Default")
      (node (ref "P2") (pin "1") (pinfunction "1_1") (pintype "power_in"))
      (node (ref "U") (pin "26") (pinfunction "USB_DN_26") (pintype "bidirectional"))
    )
    (net (code "33") (name "Net-(U-USB_DP)") (class "Default")
      (node (ref "P2") (pin "2") (pinfunction "2_2") (pintype "bidirectional"))
      (node (ref "U") (pin "25") (pinfunction "USB_DP_25") (pintype "bidirectional"))
    )
    (net (code "34") (name "Net-(U-USB_VBUS)") (class "Default")
      (node (ref "P2") (pin "3") (pinfunction "3_3") (pintype "bidirectional"))
      (node (ref "U") (pin "24") (pinfunction "USB_VBUS_24") (pintype "input"))
    )
    (net (code "35") (name "Net-(U-VRTC)") (class "Default")
      (node (ref "C1") (pin "1") (pinfunction "1_1") (pintype "passive"))
      (node (ref "U") (pin "28") (pinfunction "VRTC_28") (pintype "power_in"))
    )
    (net (code "36") (name "Net-(U2-+IN)") (class "Default")
      (node (ref "R11") (pin "2") (pinfunction "2_2") (pintype "passive"))
      (node (ref "R13") (pin "2") (pinfunction "2_2") (pintype "passive"))
      (node (ref "R9") (pin "2") (pinfunction "2_2") (pintype "passive"))
      (node (ref "U2") (pin "3") (pinfunction "+IN_3") (pintype "input"))
    )
    (net (code "37") (name "Net-(U2--IN)") (class "Default")
      (node (ref "C48") (pin "1") (pinfunction "1_1") (pintype "passive"))
      (node (ref "R10") (pin "2") (pinfunction "2_2") (pintype "passive"))
      (node (ref "R12") (pin "1") (pinfunction "1_1") (pintype "passive"))
      (node (ref "R14") (pin "2") (pinfunction "2_2") (pintype "passive"))
      (node (ref "U2") (pin "4") (pinfunction "-IN_4") (pintype "input"))
    )
    (net (code "38") (name "Net-(U2-BYPASS)") (class "Default")
      (node (ref "C35") (pin "1") (pinfunction "1_1") (pintype "passive"))
      (node (ref "R11") (pin "1") (pinfunction "1_1") (pintype "passive"))
      (node (ref "U2") (pin "2") (pinfunction "BYPASS_2") (pintype "passive"))
    )
    (net (code "39") (name "Net-(U2-VO1)") (class "Default")
      (node (ref "C48") (pin "2") (pinfunction "2_2") (pintype "passive"))
      (node (ref "J3") (pin "1") (pinfunction "1_1") (pintype "passive"))
      (node (ref "R12") (pin "2") (pinfunction "2_2") (pintype "passive"))
      (node (ref "U2") (pin "5") (pinfunction "VO1_5") (pintype "output"))
    )
    (net (code "40") (name "Net-(U2-VO2)") (class "Default")
      (node (ref "J3") (pin "2") (pinfunction "2_2") (pintype "passive"))
      (node (ref "U2") (pin "8") (pinfunction "VO2_8") (pintype "output"))
    )
    (net (code "41") (name "Net-(U10-BYPASS)") (class "Default")
      (node (ref "C101") (pin "2") (pinfunction "2_2") (pintype "passive"))
      (node (ref "U10") (pin "4") (pinfunction "BYPASS_4") (pintype "passive"))
    )
    (net (code "42") (name "VCC") (class "Default")
      (node (ref "C100") (pin "1") (pinfunction "1_1") (pintype "passive"))
      (node (ref "C2") (pin "1") (pinfunction "1_1") (pintype "passive"))
      (node (ref "C3") (pin "2") (pinfunction "2_2") (pintype "passive"))
      (node (ref "C4") (pin "2") (pinfunction "2_2") (pintype "passive"))
      (node (ref "C6") (pin "1") (pinfunction "1_1") (pintype "passive"))
      (node (ref "D1") (pin "1") (pinfunction "K_1") (pintype "passive"))
      (node (ref "R32") (pin "1") (pinfunction "1_1") (pintype "passive"))
      (node (ref "U") (pin "34") (pinfunction "VBAT_34") (pintype "power_in"))
      (node (ref "U") (pin "35") (pinfunction "VBAT_35") (pintype "power_in"))
      (node (ref "U10") (pin "1") (pinfunction "VIN_1") (pintype "power_in"))
      (node (ref "U10") (pin "3") (pinfunction "INHIBIT_3") (pintype "input"))
    )
    (net (code "43") (name "unconnected-(J-VPP-PadC6)") (class "Default")
      (node (ref "J") (pin "C6") (pinfunction "VPP_C6") (pintype "power_in+no_connect"))
    )
    (net (code "44") (name "unconnected-(U-ADC-Pad38)") (class "Default")
      (node (ref "U") (pin "38") (pinfunction "ADC_38") (pintype "input+no_connect"))
    )
    (net (code "45") (name "unconnected-(U-NETLIGHT-Pad41)") (class "Default")
      (node (ref "U") (pin "41") (pinfunction "NETLIGHT_41") (pintype "output+no_connect"))
    )
    (net (code "46") (name "unconnected-(U-RF_SYNC-Pad29)") (class "Default")
      (node (ref "U") (pin "29") (pinfunction "RF_SYNC_29") (pintype "output+no_connect"))
    )
    (net (code "47") (name "unconnected-(U-SIM_DET-Pad14)") (class "Default")
      (node (ref "U") (pin "14") (pinfunction "SIM_DET_14") (pintype "input+no_connect"))
    )
    (net (code "48") (name "unconnected-(U-STATUS-Pad42)") (class "Default")
      (node (ref "U") (pin "42") (pinfunction "STATUS_42") (pintype "output+no_connect"))
    )
    (net (code "49") (name "unconnected-(U-UART2_RXD-Pad23)") (class "Default")
      (node (ref "U") (pin "23") (pinfunction "UART2_RXD_23") (pintype "input+no_connect"))
    )
    (net (code "50") (name "unconnected-(U-UART2_TXD-Pad22)") (class "Default")
      (node (ref "U") (pin "22") (pinfunction "UART2_TXD_22") (pintype "output+no_connect"))
    )
    (net (code "51") (name "unconnected-(U-VDD_EXT-Pad40)") (class "Default")
      (node (ref "U") (pin "40") (pinfunction "VDD_EXT_40") (pintype "power_in+no_connect"))
    )
    (net (code "52") (name "unconnected-(U1-K3-Pad4)") (class "Default")
      (node (ref "U1") (pin "4") (pinfunction "K3_4") (pintype "passive+no_connect"))
    )
  )
)
